# IQ_Modulator.net
KiCad netlist of a schematic drawn in Altium Designer
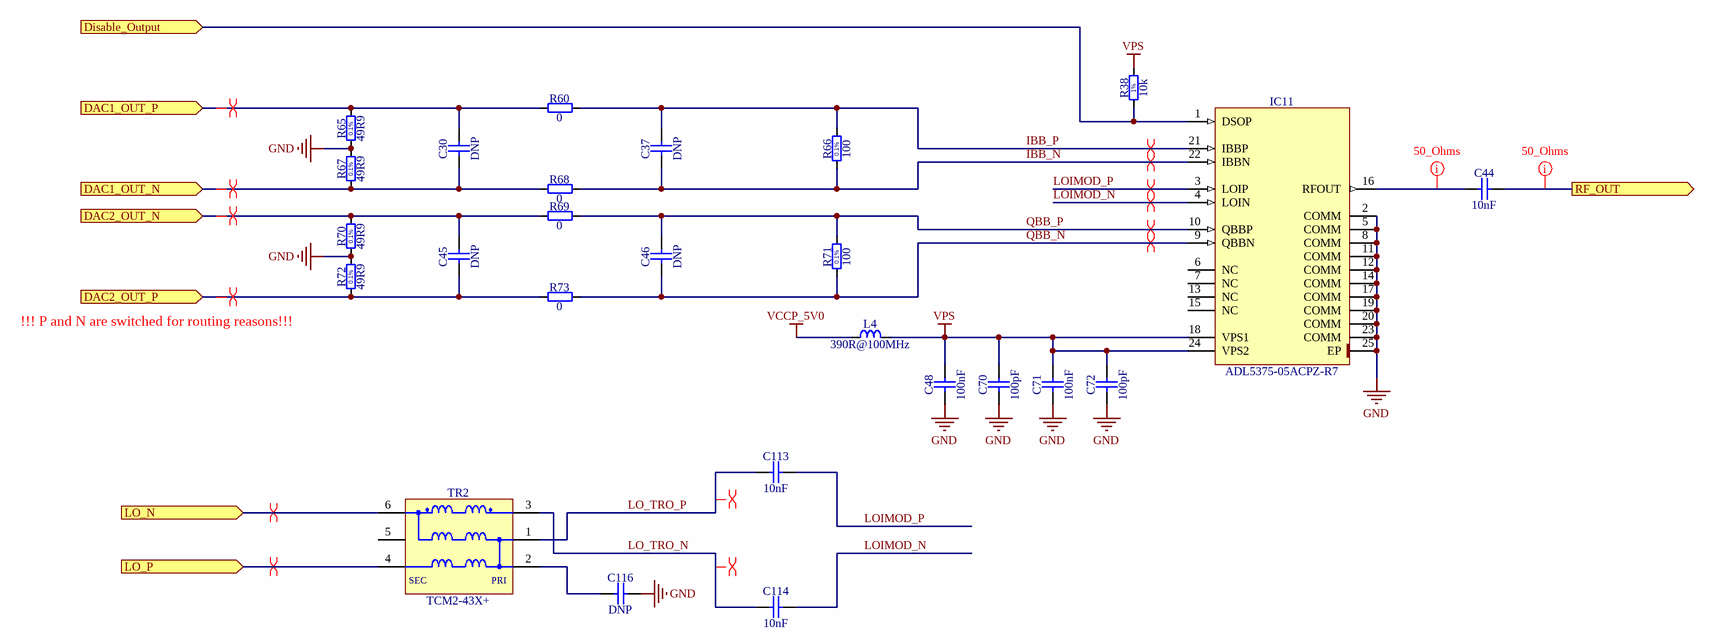
[diagram p0: IQ_Modulator.SchDoc]

(export (version "E")
  (design (tool "Eeschema 10.0.6"))
  (components
    (comp (ref "C30")
      (value "DNP")
      (footprint "CAPC1005X55N")
      (description "Non-polarised capacitor")
      (fields
        (field (name "PART NUMBER") "CC0402_1.5NF_50V_10%_X7R")
        (field (name "VOLTAGE") "50V")
        (field (name "AUTHOR") "CERN DEM JLC")
      )
      (libsource (lib "Capacitors") (part "Capacitor - non polarized"))
    )
    (comp (ref "C37")
      (value "DNP")
      (footprint "CAPC1005X55N")
      (description "Non-polarised capacitor")
      (fields
        (field (name "PART NUMBER") "CC0402_1.5NF_50V_10%_X7R")
        (field (name "VOLTAGE") "50V")
        (field (name "AUTHOR") "CERN DEM JLC")
      )
      (libsource (lib "Capacitors") (part "Capacitor - non polarized"))
    )
    (comp (ref "C44")
      (value "10nF")
      (footprint "CAPC1005X55N")
      (description "Non-polarised capacitor")
      (fields
        (field (name "PART NUMBER") "CC0402_10NF_16V_10%_X7R")
        (field (name "VOLTAGE") "16V")
        (field (name "AUTHOR") "CERN DEM JLC")
      )
      (libsource (lib "Capacitors") (part "Capacitor - non polarized"))
    )
    (comp (ref "C45")
      (value "DNP")
      (footprint "CAPC1005X55N")
      (description "Non-polarised capacitor")
      (fields
        (field (name "PART NUMBER") "CC0402_1.5NF_50V_10%_X7R")
        (field (name "VOLTAGE") "50V")
        (field (name "AUTHOR") "CERN DEM JLC")
      )
      (libsource (lib "Capacitors") (part "Capacitor - non polarized"))
    )
    (comp (ref "C46")
      (value "DNP")
      (footprint "CAPC1005X55N")
      (description "Non-polarised capacitor")
      (fields
        (field (name "PART NUMBER") "CC0402_1.5NF_50V_10%_X7R")
        (field (name "VOLTAGE") "50V")
        (field (name "AUTHOR") "CERN DEM JLC")
      )
      (libsource (lib "Capacitors") (part "Capacitor - non polarized"))
    )
    (comp (ref "C48")
      (value "100nF")
      (footprint "CAPC1005X55N")
      (description "Non-polarised capacitor")
      (fields
        (field (name "PART NUMBER") "CC0402_100NF_16V_10%_X7R")
        (field (name "VOLTAGE") "16V")
        (field (name "AUTHOR") "CERN DEM JLC")
      )
      (libsource (lib "Capacitors") (part "Capacitor - non polarized"))
    )
    (comp (ref "C70")
      (value "100pF")
      (footprint "CAPC1005X55N")
      (description "Non-polarised capacitor")
      (fields
        (field (name "PART NUMBER") "CC0402_100PF_50V_5%_C0G")
        (field (name "VOLTAGE") "50V")
        (field (name "AUTHOR") "CERN DEM JLC")
      )
      (libsource (lib "Capacitors") (part "Capacitor - non polarized"))
    )
    (comp (ref "C71")
      (value "100nF")
      (footprint "CAPC1005X55N")
      (description "Non-polarised capacitor")
      (fields
        (field (name "PART NUMBER") "CC0402_100NF_16V_10%_X7R")
        (field (name "VOLTAGE") "16V")
        (field (name "AUTHOR") "CERN DEM JLC")
      )
      (libsource (lib "Capacitors") (part "Capacitor - non polarized"))
    )
    (comp (ref "C72")
      (value "100pF")
      (footprint "CAPC1005X55N")
      (description "Non-polarised capacitor")
      (fields
        (field (name "PART NUMBER") "CC0402_100PF_50V_5%_C0G")
        (field (name "VOLTAGE") "50V")
        (field (name "AUTHOR") "CERN DEM JLC")
      )
      (libsource (lib "Capacitors") (part "Capacitor - non polarized"))
    )
    (comp (ref "C113")
      (value "10nF")
      (footprint "CAPC1005X55N")
      (description "Non-polarised capacitor")
      (fields
        (field (name "PART NUMBER") "CC0402_10NF_16V_10%_X7R")
        (field (name "VOLTAGE") "16V")
        (field (name "AUTHOR") "CERN DEM JLC")
      )
      (libsource (lib "Capacitors") (part "Capacitor - non polarized"))
    )
    (comp (ref "C114")
      (value "10nF")
      (footprint "CAPC1005X55N")
      (description "Non-polarised capacitor")
      (fields
        (field (name "PART NUMBER") "CC0402_10NF_16V_10%_X7R")
        (field (name "VOLTAGE") "16V")
        (field (name "AUTHOR") "CERN DEM JLC")
      )
      (libsource (lib "Capacitors") (part "Capacitor - non polarized"))
    )
    (comp (ref "C116")
      (value "DNP")
      (footprint "CAPC1005X55N")
      (description "Non-polarised capacitor")
      (fields
        (field (name "PART NUMBER") "CC0402_100PF_50V_5%_C0G")
        (field (name "VOLTAGE") "50V")
        (field (name "AUTHOR") "CERN DEM JLC")
      )
      (libsource (lib "Capacitors") (part "Capacitor - non polarized"))
    )
    (comp (ref "IC11")
      (value "ADL5375-05ACPZ-R7")
      (footprint "QFN50P400X400X100-25N-S265")
      (description "400 MHz to 6 GHz Broadband Quadrature Modulator")
      (fields (field (name "MANUFACTURER") "ANALOG DEVICES") (field (name "AUTHOR") "CERN DEM JLC"))
      (libsource (lib "ICs And Semiconductors") (part "ADL5375"))
    )
    (comp (ref "L4")
      (value "390R@100MHz")
      (footprint "INDC1608X95N")
      (description "Inductor")
      (fields
        (field (name "PART NUMBER") "IND0603_TDK_MPZ1608R391A")
        (field (name "POWER") "1.2A")
        (field (name "AUTHOR") "CERN DEM JLC")
      )
      (libsource (lib "Inductors & Transformers") (part "Inductor"))
    )
    (comp (ref "R38")
      (value "10k")
      (footprint "RESC1005X40N")
      (description "Resistor - 1%")
      (fields
        (field (name "PART NUMBER") "R0402_10K_1%_0.0625W_100PPM")
        (field (name "POWER") "0.0625W")
        (field (name "AUTHOR") "CERN DEM JLC")
      )
      (libsource (lib "Resistors") (part "Resistor - 1%"))
    )
    (comp (ref "R60")
      (value "0")
      (footprint "RESC1005X40N")
      (description "Resistor")
      (fields
        (field (name "PART NUMBER") "R0402_0R_JUMPER")
        (field (name "MANUFACTURER") "GENERIC")
        (field (name "AUTHOR") "CERN DEM JLC")
      )
      (libsource (lib "Resistors") (part "Resistor"))
    )
    (comp (ref "R65")
      (value "49R9")
      (footprint "RESC1005X35N")
      (description "Resistor - 0.1%")
      (fields
        (field (name "PART NUMBER") "R0402_49R9_0.1%_0.063W_25PPM")
        (field (name "POWER") "0.063W")
        (field (name "AUTHOR") "CERN DEM JMW")
      )
      (libsource (lib "Resistors") (part "Resistor - 0.1%"))
    )
    (comp (ref "R66")
      (value "100")
      (footprint "RESC1005X35N")
      (description "Resistor - 0.1%")
      (fields
        (field (name "PART NUMBER") "R0402_100R_0.1%_0.063W_25PPM")
        (field (name "POWER") "0.063W")
        (field (name "AUTHOR") "CERN DEM JMW")
      )
      (libsource (lib "Resistors") (part "Resistor - 0.1%"))
    )
    (comp (ref "R67")
      (value "49R9")
      (footprint "RESC1005X35N")
      (description "Resistor - 0.1%")
      (fields
        (field (name "PART NUMBER") "R0402_49R9_0.1%_0.063W_25PPM")
        (field (name "POWER") "0.063W")
        (field (name "AUTHOR") "CERN DEM JMW")
      )
      (libsource (lib "Resistors") (part "Resistor - 0.1%"))
    )
    (comp (ref "R68")
      (value "0")
      (footprint "RESC1005X40N")
      (description "Resistor")
      (fields
        (field (name "PART NUMBER") "R0402_0R_JUMPER")
        (field (name "MANUFACTURER") "GENERIC")
        (field (name "AUTHOR") "CERN DEM JLC")
      )
      (libsource (lib "Resistors") (part "Resistor"))
    )
    (comp (ref "R69")
      (value "0")
      (footprint "RESC1005X40N")
      (description "Resistor")
      (fields
        (field (name "PART NUMBER") "R0402_0R_JUMPER")
        (field (name "MANUFACTURER") "GENERIC")
        (field (name "AUTHOR") "CERN DEM JLC")
      )
      (libsource (lib "Resistors") (part "Resistor"))
    )
    (comp (ref "R70")
      (value "49R9")
      (footprint "RESC1005X35N")
      (description "Resistor - 0.1%")
      (fields
        (field (name "PART NUMBER") "R0402_49R9_0.1%_0.063W_25PPM")
        (field (name "POWER") "0.063W")
        (field (name "AUTHOR") "CERN DEM JMW")
      )
      (libsource (lib "Resistors") (part "Resistor - 0.1%"))
    )
    (comp (ref "R71")
      (value "100")
      (footprint "RESC1005X35N")
      (description "Resistor - 0.1%")
      (fields
        (field (name "PART NUMBER") "R0402_100R_0.1%_0.063W_25PPM")
        (field (name "POWER") "0.063W")
        (field (name "AUTHOR") "CERN DEM JMW")
      )
      (libsource (lib "Resistors") (part "Resistor - 0.1%"))
    )
    (comp (ref "R72")
      (value "49R9")
      (footprint "RESC1005X35N")
      (description "Resistor - 0.1%")
      (fields
        (field (name "PART NUMBER") "R0402_49R9_0.1%_0.063W_25PPM")
        (field (name "POWER") "0.063W")
        (field (name "AUTHOR") "CERN DEM JMW")
      )
      (libsource (lib "Resistors") (part "Resistor - 0.1%"))
    )
    (comp (ref "R73")
      (value "0")
      (footprint "RESC1005X40N")
      (description "Resistor")
      (fields
        (field (name "PART NUMBER") "R0402_0R_JUMPER")
        (field (name "MANUFACTURER") "GENERIC")
        (field (name "AUTHOR") "CERN DEM JLC")
      )
      (libsource (lib "Resistors") (part "Resistor"))
    )
    (comp (ref "TR2")
      (value "TCM2-43X+")
      (footprint "XFMR_MINI-CIRCUITS_DB1627")
      (description "50 OHMS 10 to 4000 MHz RF Transformer")
      (fields
        (field (name "PART NUMBER") "XFMR_MINI-CIRCUITS_TCM2-43X+")
        (field (name "POWER") "0.4W")
        (field (name "AUTHOR") "CERN DEM BC")
      )
      (libsource (lib "Inductors & Transformers") (part "XFMR_MINI-CIRCUITS_TCM2-43X"))
    )
  )
  (nets
    (net (code "1") (name "/DAC1_OUT_N") (class "Default")
      (node (ref "C30") (pin "1") (pinfunction "1_1") (pintype "passive"))
      (node (ref "R67") (pin "1") (pinfunction "1_1") (pintype "passive"))
      (node (ref "R68") (pin "1") (pinfunction "1_1") (pintype "passive"))
    )
    (net (code "2") (name "/DAC1_OUT_P") (class "Default")
      (node (ref "C30") (pin "2") (pinfunction "2_2") (pintype "passive"))
      (node (ref "R60") (pin "1") (pinfunction "1_1") (pintype "passive"))
      (node (ref "R65") (pin "2") (pinfunction "2_2") (pintype "passive"))
    )
    (net (code "3") (name "/DAC2_OUT_N") (class "Default")
      (node (ref "C45") (pin "2") (pinfunction "2_2") (pintype "passive"))
      (node (ref "R69") (pin "1") (pinfunction "1_1") (pintype "passive"))
      (node (ref "R70") (pin "2") (pinfunction "2_2") (pintype "passive"))
    )
    (net (code "4") (name "/DAC2_OUT_P") (class "Default")
      (node (ref "C45") (pin "1") (pinfunction "1_1") (pintype "passive"))
      (node (ref "R72") (pin "1") (pinfunction "1_1") (pintype "passive"))
      (node (ref "R73") (pin "1") (pinfunction "1_1") (pintype "passive"))
    )
    (net (code "5") (name "/Disable_Output") (class "Default")
      (node (ref "IC11") (pin "1") (pinfunction "DSOP_1") (pintype "input"))
      (node (ref "R38") (pin "1") (pinfunction "1_1") (pintype "passive"))
    )
    (net (code "6") (name "/IBB_N") (class "Default")
      (node (ref "C37") (pin "1") (pinfunction "1_1") (pintype "passive"))
      (node (ref "IC11") (pin "22") (pinfunction "IBBN_22") (pintype "input"))
      (node (ref "R66") (pin "1") (pinfunction "1_1") (pintype "passive"))
      (node (ref "R68") (pin "2") (pinfunction "2_2") (pintype "passive"))
    )
    (net (code "7") (name "/IBB_P") (class "Default")
      (node (ref "C37") (pin "2") (pinfunction "2_2") (pintype "passive"))
      (node (ref "IC11") (pin "21") (pinfunction "IBBP_21") (pintype "input"))
      (node (ref "R60") (pin "2") (pinfunction "2_2") (pintype "passive"))
      (node (ref "R66") (pin "2") (pinfunction "2_2") (pintype "passive"))
    )
    (net (code "8") (name "/LOIMOD_N") (class "Default")
      (node (ref "C114") (pin "2") (pinfunction "2_2") (pintype "passive"))
      (node (ref "IC11") (pin "4") (pinfunction "LOIN_4") (pintype "input"))
    )
    (net (code "9") (name "/LOIMOD_P") (class "Default")
      (node (ref "C113") (pin "2") (pinfunction "2_2") (pintype "passive"))
      (node (ref "IC11") (pin "3") (pinfunction "LOIP_3") (pintype "input"))
    )
    (net (code "10") (name "/LO_N") (class "Default")
      (node (ref "TR2") (pin "6") (pinfunction "S1_6") (pintype "passive"))
    )
    (net (code "11") (name "/LO_P") (class "Default")
      (node (ref "TR2") (pin "4") (pinfunction "S1_4") (pintype "passive"))
    )
    (net (code "12") (name "/LO_TRO_N") (class "Default")
      (node (ref "C114") (pin "1") (pinfunction "1_1") (pintype "passive"))
      (node (ref "TR2") (pin "3") (pinfunction "P1_3") (pintype "passive"))
    )
    (net (code "13") (name "/LO_TRO_P") (class "Default")
      (node (ref "C113") (pin "1") (pinfunction "1_1") (pintype "passive"))
      (node (ref "TR2") (pin "1") (pinfunction "P1_1") (pintype "passive"))
    )
    (net (code "14") (name "/QBB_N") (class "Default")
      (node (ref "C46") (pin "1") (pinfunction "1_1") (pintype "passive"))
      (node (ref "IC11") (pin "9") (pinfunction "QBBN_9") (pintype "input"))
      (node (ref "R71") (pin "1") (pinfunction "1_1") (pintype "passive"))
      (node (ref "R73") (pin "2") (pinfunction "2_2") (pintype "passive"))
    )
    (net (code "15") (name "/QBB_P") (class "Default")
      (node (ref "C46") (pin "2") (pinfunction "2_2") (pintype "passive"))
      (node (ref "IC11") (pin "10") (pinfunction "QBBP_10") (pintype "input"))
      (node (ref "R69") (pin "2") (pinfunction "2_2") (pintype "passive"))
      (node (ref "R71") (pin "2") (pinfunction "2_2") (pintype "passive"))
    )
    (net (code "16") (name "/RF_OUT") (class "Default")
      (node (ref "C44") (pin "2") (pinfunction "2_2") (pintype "passive"))
    )
    (net (code "17") (name "GND") (class "Default")
      (node (ref "C116") (pin "2") (pinfunction "2_2") (pintype "passive"))
      (node (ref "C48") (pin "1") (pinfunction "1_1") (pintype "passive"))
      (node (ref "C70") (pin "1") (pinfunction "1_1") (pintype "passive"))
      (node (ref "C71") (pin "1") (pinfunction "1_1") (pintype "passive"))
      (node (ref "C72") (pin "1") (pinfunction "1_1") (pintype "passive"))
      (node (ref "IC11") (pin "11") (pinfunction "COMM_11") (pintype "power_in"))
      (node (ref "IC11") (pin "12") (pinfunction "COMM_12") (pintype "power_in"))
      (node (ref "IC11") (pin "14") (pinfunction "COMM_14") (pintype "power_in"))
      (node (ref "IC11") (pin "17") (pinfunction "COMM_17") (pintype "power_in"))
      (node (ref "IC11") (pin "19") (pinfunction "COMM_19") (pintype "power_in"))
      (node (ref "IC11") (pin "2") (pinfunction "COMM_2") (pintype "power_in"))
      (node (ref "IC11") (pin "20") (pinfunction "COMM_20") (pintype "power_in"))
      (node (ref "IC11") (pin "23") (pinfunction "COMM_23") (pintype "power_in"))
      (node (ref "IC11") (pin "25") (pinfunction "EP_25") (pintype "power_in"))
      (node (ref "IC11") (pin "5") (pinfunction "COMM_5") (pintype "power_in"))
      (node (ref "IC11") (pin "8") (pinfunction "COMM_8") (pintype "power_in"))
      (node (ref "R65") (pin "1") (pinfunction "1_1") (pintype "passive"))
      (node (ref "R67") (pin "2") (pinfunction "2_2") (pintype "passive"))
      (node (ref "R70") (pin "1") (pinfunction "1_1") (pintype "passive"))
      (node (ref "R72") (pin "2") (pinfunction "2_2") (pintype "passive"))
    )
    (net (code "18") (name "Net-(C116-Pad1)") (class "Default")
      (node (ref "C116") (pin "1") (pinfunction "1_1") (pintype "passive"))
      (node (ref "TR2") (pin "2") (pinfunction "P1_2") (pintype "passive"))
    )
    (net (code "19") (name "Net-(IC11-RFOUT)") (class "Default")
      (node (ref "C44") (pin "1") (pinfunction "1_1") (pintype "passive"))
      (node (ref "IC11") (pin "16") (pinfunction "RFOUT_16") (pintype "output"))
    )
    (net (code "20") (name "VCCP_5V0") (class "Default")
      (node (ref "L4") (pin "1") (pinfunction "1_1") (pintype "passive"))
    )
    (net (code "21") (name "VPS") (class "Default")
      (node (ref "C48") (pin "2") (pinfunction "2_2") (pintype "passive"))
      (node (ref "C70") (pin "2") (pinfunction "2_2") (pintype "passive"))
      (node (ref "C71") (pin "2") (pinfunction "2_2") (pintype "passive"))
      (node (ref "C72") (pin "2") (pinfunction "2_2") (pintype "passive"))
      (node (ref "IC11") (pin "18") (pinfunction "VPS1_18") (pintype "power_in"))
      (node (ref "IC11") (pin "24") (pinfunction "VPS2_24") (pintype "power_in"))
      (node (ref "L4") (pin "2") (pinfunction "2_2") (pintype "passive"))
      (node (ref "R38") (pin "2") (pinfunction "2_2") (pintype "passive"))
    )
    (net (code "22") (name "unconnected-(IC11-NC-Pad6)") (class "Default")
      (node (ref "IC11") (pin "6") (pinfunction "NC_6") (pintype "passive"))
    )
    (net (code "23") (name "unconnected-(IC11-NC-Pad7)") (class "Default")
      (node (ref "IC11") (pin "7") (pinfunction "NC_7") (pintype "passive"))
    )
    (net (code "24") (name "unconnected-(IC11-NC-Pad13)") (class "Default")
      (node (ref "IC11") (pin "13") (pinfunction "NC_13") (pintype "passive"))
    )
    (net (code "25") (name "unconnected-(IC11-NC-Pad15)") (class "Default")
      (node (ref "IC11") (pin "15") (pinfunction "NC_15") (pintype "passive"))
    )
    (net (code "26") (name "unconnected-(TR2-NC-Pad5)") (class "Default")
      (node (ref "TR2") (pin "5") (pinfunction "NC_5") (pintype "passive"))
    )
  )
)
